# BarometricPressureSensor.net
KiCad netlist of a schematic drawn in Altium Designer
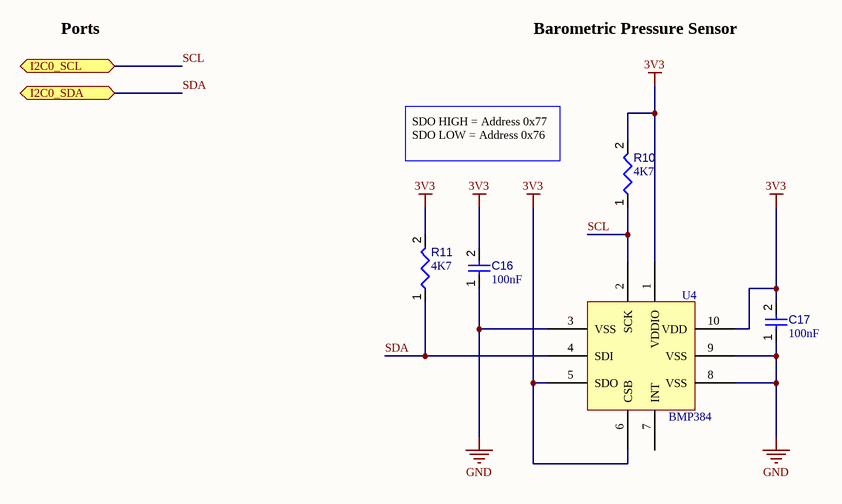
[diagram p0: BarometricPressureSensor.SchDoc]

(export (version "E")
  (design (tool "Eeschema 10.0.6"))
  (components
    (comp (ref "C16")
      (value "100nF")
      (footprint "CAPC0805(2012)145_L")
      (description "Chip Capacitor, 100nF +/-20%, 25V, 0805, Thickness 1.45 mm")
      (fields (field (name "TOLERANCE") "10%") (field (name "Comment") "Capacitor 100nF +/-20% 25V 0805"))
      (libsource (lib "James Cook University") (part "CAP-NP-2"))
    )
    (comp (ref "C17")
      (value "100nF")
      (footprint "CAPC0805(2012)145_L")
      (description "Chip Capacitor, 100nF +/-20%, 25V, 0805, Thickness 1.45 mm")
      (fields (field (name "TOLERANCE") "10%") (field (name "Comment") "Capacitor 100nF +/-20% 25V 0805"))
      (libsource (lib "James Cook University") (part "CAP-NP-2"))
    )
    (comp (ref "R10")
      (value "4K7")
      (footprint "RESC0805(2012)_L")
      (description "4K7 0.125W 5% 0805 (2012 Metric)  SMD")
      (fields (field (name "POWER") "0.125W") (field (name "TOLERANCE") "5%"))
      (libsource (lib "James Cook University") (part "1KR5J"))
    )
    (comp (ref "R11")
      (value "4K7")
      (footprint "RESC0805(2012)_L")
      (description "4K7 0.125W 5% 0805 (2012 Metric)  SMD")
      (fields (field (name "POWER") "0.125W") (field (name "TOLERANCE") "5%"))
      (libsource (lib "James Cook University") (part "1KR5J"))
    )
    (comp (ref "U4")
      (value "BMP384")
      (footprint "BMP384 LGA 2.0x2.0x0.95mm 10pin")
      (description "Bosch BMP384 Barometric Pressure Sensor")
      (libsource (lib "CC3501_Misc_Symbols") (part "BMP384 Barometric Pressure Sensor"))
    )
  )
  (nets
    (net (code "1") (name "/SCL") (class "Default")
      (node (ref "R10") (pin "1") (pinfunction "1_1") (pintype "passive"))
      (node (ref "U4") (pin "2") (pinfunction "SCK_2") (pintype "passive"))
    )
    (net (code "2") (name "/SDA") (class "Default")
      (node (ref "R11") (pin "1") (pinfunction "1_1") (pintype "passive"))
      (node (ref "U4") (pin "4") (pinfunction "SDI_4") (pintype "passive"))
    )
    (net (code "3") (name "3V3") (class "Default")
      (node (ref "C16") (pin "2") (pinfunction "2_2") (pintype "passive"))
      (node (ref "C17") (pin "2") (pinfunction "2_2") (pintype "passive"))
      (node (ref "R10") (pin "2") (pinfunction "2_2") (pintype "passive"))
      (node (ref "R11") (pin "2") (pinfunction "2_2") (pintype "passive"))
      (node (ref "U4") (pin "1") (pinfunction "VDDIO_1") (pintype "power_in"))
      (node (ref "U4") (pin "10") (pinfunction "VDD_10") (pintype "power_in"))
      (node (ref "U4") (pin "5") (pinfunction "SDO_5") (pintype "passive"))
      (node (ref "U4") (pin "6") (pinfunction "CSB_6") (pintype "passive"))
    )
    (net (code "4") (name "GND") (class "Default")
      (node (ref "C16") (pin "1") (pinfunction "1_1") (pintype "passive"))
      (node (ref "C17") (pin "1") (pinfunction "1_1") (pintype "passive"))
      (node (ref "U4") (pin "3") (pinfunction "VSS_3") (pintype "power_in"))
      (node (ref "U4") (pin "8") (pinfunction "VSS_8") (pintype "power_in"))
      (node (ref "U4") (pin "9") (pinfunction "VSS_9") (pintype "power_in"))
    )
    (net (code "5") (name "unconnected-(U4-INT-Pad7)") (class "Default")
      (node (ref "U4") (pin "7") (pinfunction "INT_7") (pintype "passive"))
    )
  )
)
